# WaterMonitor.net
KiCad netlist of a schematic drawn in EAGLE
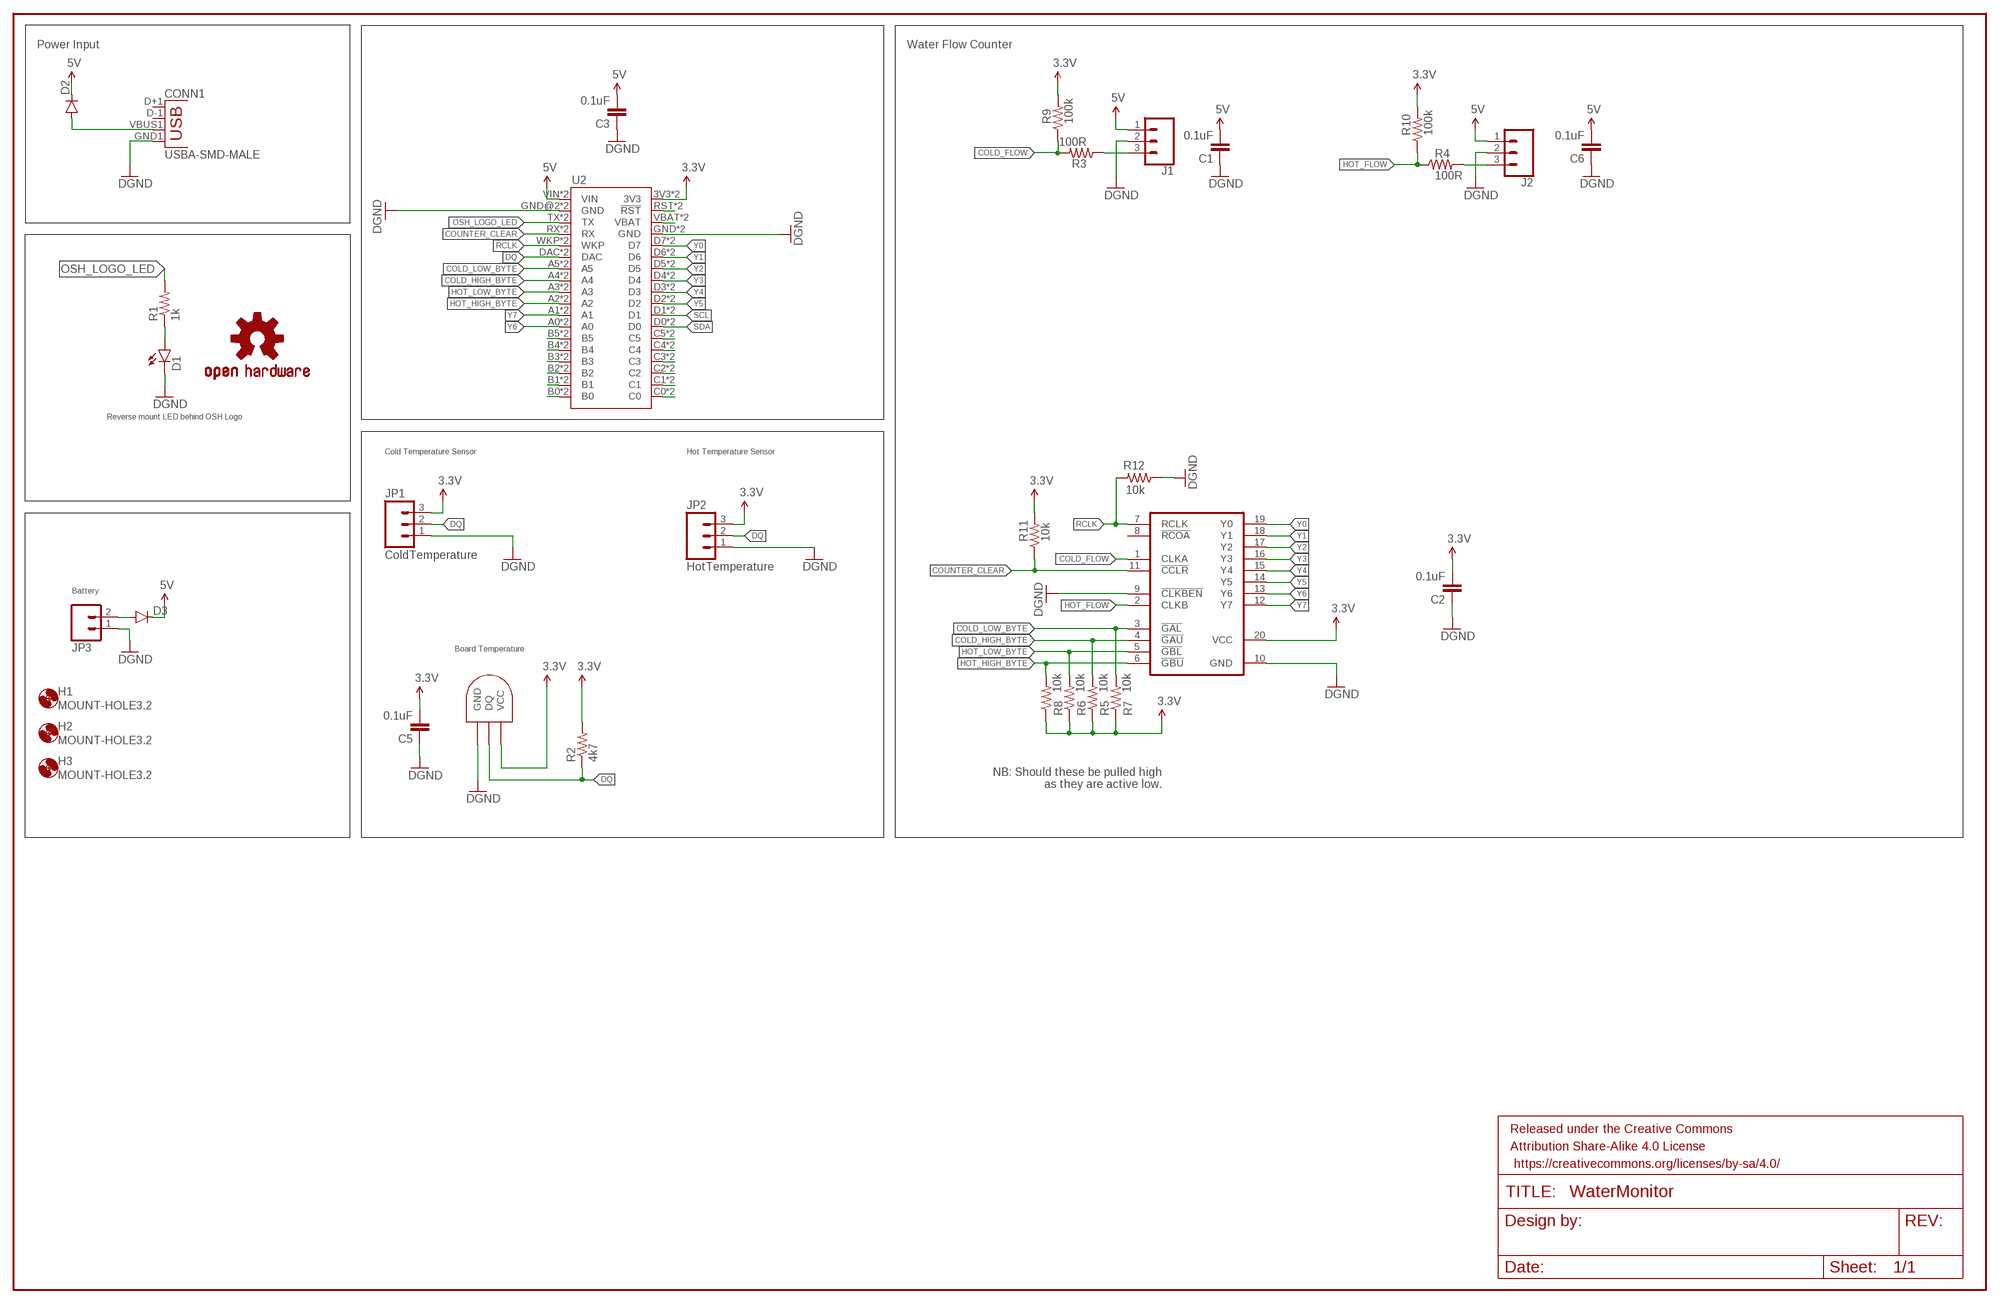
[diagram p0: schematic, sheet 1]

(export (version "E")
  (design (tool "Eeschema 10.0.6"))
  (components
    (comp (ref "C1")
      (value "0.1uF")
      (footprint "eagle-import:0805")
      (libsource (lib "eagle-import") (part "CAP0805"))
    )
    (comp (ref "C2")
      (value "0.1uF")
      (footprint "eagle-import:0805")
      (libsource (lib "eagle-import") (part "CAP0805"))
    )
    (comp (ref "C3")
      (value "0.1uF")
      (footprint "eagle-import:0805")
      (libsource (lib "eagle-import") (part "CAP0805"))
    )
    (comp (ref "C5")
      (value "0.1uF")
      (footprint "eagle-import:0805")
      (libsource (lib "eagle-import") (part "CAP0805"))
    )
    (comp (ref "C6")
      (value "0.1uF")
      (footprint "eagle-import:0805")
      (libsource (lib "eagle-import") (part "CAP0805"))
    )
    (comp (ref "CONN1")
      (value "USBA-SMD-MALE")
      (footprint "eagle-import:USB-A-SMT-MALE")
      (libsource (lib "eagle-import") (part "USBA-SMD-MALE"))
    )
    (comp (ref "D1")
      (value "LED1206-BOTTOM")
      (footprint "eagle-import:LED-1206-BOTTOM")
      (libsource (lib "eagle-import") (part "LED1206-BOTTOM"))
    )
    (comp (ref "D2")
      (value "DIODESMA")
      (footprint "eagle-import:SMA-DIODE")
      (libsource (lib "eagle-import") (part "DIODESMA"))
    )
    (comp (ref "D3")
      (value "DIODESMA")
      (footprint "eagle-import:SMA-DIODE")
      (libsource (lib "eagle-import") (part "DIODESMA"))
    )
    (comp (ref "FRAME2")
      (value "FRAME-LEDGER")
      (footprint "eagle-import:CREATIVE_COMMONS")
      (libsource (lib "eagle-import") (part "FRAME-LEDGER"))
    )
    (comp (ref "H1")
      (value "MOUNT-HOLE3.2")
      (footprint "eagle-import:3,2")
      (libsource (lib "eagle-import") (part "MOUNT-HOLE3.2"))
    )
    (comp (ref "H2")
      (value "MOUNT-HOLE3.2")
      (footprint "eagle-import:3,2")
      (libsource (lib "eagle-import") (part "MOUNT-HOLE3.2"))
    )
    (comp (ref "H3")
      (value "MOUNT-HOLE3.2")
      (footprint "eagle-import:3,2")
      (libsource (lib "eagle-import") (part "MOUNT-HOLE3.2"))
    )
    (comp (ref "J1")
      (value "CONN_03JST-HX-PTH-VERT")
      (footprint "eagle-import:JST-HX-3-PTH-VERT")
      (libsource (lib "eagle-import") (part "CONN_03JST-HX-PTH-VERT"))
    )
    (comp (ref "J2")
      (value "CONN_03JST-HX-PTH-VERT")
      (footprint "eagle-import:JST-HX-3-PTH-VERT")
      (libsource (lib "eagle-import") (part "CONN_03JST-HX-PTH-VERT"))
    )
    (comp (ref "JP1")
      (value "ColdTemperature")
      (footprint "eagle-import:MOLEX-1X3")
      (libsource (lib "eagle-import") (part "M03POLAR"))
    )
    (comp (ref "JP2")
      (value "HotTemperature")
      (footprint "eagle-import:MOLEX-1X3")
      (libsource (lib "eagle-import") (part "M03POLAR"))
    )
    (comp (ref "JP3")
      (value "M02-JST-2MM-SMT")
      (footprint "eagle-import:JST-2-SMD")
      (libsource (lib "eagle-import") (part "M02-JST-2MM-SMT"))
    )
    (comp (ref "LOGO1")
      (value "OSHW-LOGOM")
      (footprint "eagle-import:OSHW-LOGO-M")
      (libsource (lib "eagle-import") (part "OSHW-LOGOM"))
    )
    (comp (ref "R1")
      (value "1k")
      (footprint "eagle-import:1206")
      (libsource (lib "eagle-import") (part "RESISTOR1206"))
    )
    (comp (ref "R2")
      (value "4k7")
      (footprint "eagle-import:0805")
      (libsource (lib "eagle-import") (part "RESISTOR0805-RES"))
    )
    (comp (ref "R3")
      (value "100R")
      (footprint "eagle-import:0805")
      (libsource (lib "eagle-import") (part "RESISTOR0805-RES"))
    )
    (comp (ref "R4")
      (value "100R")
      (footprint "eagle-import:0805")
      (libsource (lib "eagle-import") (part "RESISTOR0805-RES"))
    )
    (comp (ref "R5")
      (value "10k")
      (footprint "eagle-import:0805")
      (libsource (lib "eagle-import") (part "RESISTOR0805-RES"))
    )
    (comp (ref "R6")
      (value "10k")
      (footprint "eagle-import:0805")
      (libsource (lib "eagle-import") (part "RESISTOR0805-RES"))
    )
    (comp (ref "R7")
      (value "10k")
      (footprint "eagle-import:0805")
      (libsource (lib "eagle-import") (part "RESISTOR0805-RES"))
    )
    (comp (ref "R8")
      (value "10k")
      (footprint "eagle-import:0805")
      (libsource (lib "eagle-import") (part "RESISTOR0805-RES"))
    )
    (comp (ref "R9")
      (value "100k")
      (footprint "eagle-import:0805")
      (libsource (lib "eagle-import") (part "RESISTOR0805-RES"))
    )
    (comp (ref "R10")
      (value "100k")
      (footprint "eagle-import:0805")
      (libsource (lib "eagle-import") (part "RESISTOR0805-RES"))
    )
    (comp (ref "R11")
      (value "10k")
      (footprint "eagle-import:0805")
      (libsource (lib "eagle-import") (part "RESISTOR0805-RES"))
    )
    (comp (ref "R12")
      (value "10k")
      (footprint "eagle-import:0805")
      (libsource (lib "eagle-import") (part "RESISTOR0805-RES"))
    )
    (comp (ref "U1")
      (value "SN74LV8154PW")
      (footprint "eagle-import:TSSOP20")
      (libsource (lib "eagle-import") (part "SN74LV8154PW"))
    )
    (comp (ref "U2")
      (value "ELECTRONDUALNAMED")
      (footprint "eagle-import:ELECTRON_SIMPLE_SILK_NAMES_DUAL")
      (libsource (lib "eagle-import") (part "ELECTRONDUALNAMED"))
    )
    (comp (ref "U4")
      (value "DS1820SOIC")
      (footprint "eagle-import:DS18B20_SOIC")
      (libsource (lib "eagle-import") (part "DS1820SOIC"))
    )
  )
  (nets
    (net (code "1") (name "3.3V") (class "Default")
      (node (ref "C2") (pin "2") (pinfunction "2_2") (pintype "passive"))
      (node (ref "C5") (pin "2") (pinfunction "2_2") (pintype "passive"))
      (node (ref "JP1") (pin "3") (pinfunction "3_3") (pintype "passive"))
      (node (ref "JP2") (pin "3") (pinfunction "3_3") (pintype "passive"))
      (node (ref "R10") (pin "2") (pinfunction "2_2") (pintype "passive"))
      (node (ref "R11") (pin "2") (pinfunction "2_2") (pintype "passive"))
      (node (ref "R2") (pin "2") (pinfunction "2_2") (pintype "passive"))
      (node (ref "R5") (pin "1") (pinfunction "1_1") (pintype "passive"))
      (node (ref "R6") (pin "1") (pinfunction "1_1") (pintype "passive"))
      (node (ref "R7") (pin "1") (pinfunction "1_1") (pintype "passive"))
      (node (ref "R8") (pin "1") (pinfunction "1_1") (pintype "passive"))
      (node (ref "R9") (pin "2") (pinfunction "2_2") (pintype "passive"))
      (node (ref "U1") (pin "20") (pinfunction "VCC_20") (pintype "power_in"))
      (node (ref "U2") (pin "3V3") (pinfunction "3V3_3V3") (pintype "power_in"))
      (node (ref "U2") (pin "3V3_1") (pinfunction "3V3_3V3_1") (pintype "power_in"))
      (node (ref "U4") (pin "VCC") (pinfunction "VCC_VCC") (pintype "power_in"))
    )
    (net (code "2") (name "5V") (class "Default")
      (node (ref "C1") (pin "2") (pinfunction "2_2") (pintype "passive"))
      (node (ref "C3") (pin "2") (pinfunction "2_2") (pintype "passive"))
      (node (ref "C6") (pin "2") (pinfunction "2_2") (pintype "passive"))
      (node (ref "D2") (pin "C") (pinfunction "C_C") (pintype "passive"))
      (node (ref "D3") (pin "C") (pinfunction "C_C") (pintype "passive"))
      (node (ref "J1") (pin "1") (pinfunction "1_1") (pintype "passive"))
      (node (ref "J2") (pin "1") (pinfunction "1_1") (pintype "passive"))
      (node (ref "U2") (pin "VIN") (pinfunction "VIN_VIN") (pintype "power_in"))
      (node (ref "U2") (pin "VIN_1B") (pinfunction "VIN_VIN_1B") (pintype "power_in"))
    )
    (net (code "3") (name "COLD_FLOW") (class "Default")
      (node (ref "R3") (pin "2") (pinfunction "2_2") (pintype "passive"))
      (node (ref "R9") (pin "1") (pinfunction "1_1") (pintype "passive"))
      (node (ref "U1") (pin "1") (pinfunction "CLKA_1") (pintype "input"))
    )
    (net (code "4") (name "COLD_HIGH_BYTE") (class "Default")
      (node (ref "R5") (pin "2") (pinfunction "2_2") (pintype "passive"))
      (node (ref "U1") (pin "4") (pinfunction "~{GAU}_4") (pintype "input"))
      (node (ref "U2") (pin "A4") (pinfunction "A4_A4") (pintype "bidirectional"))
      (node (ref "U2") (pin "A4_1") (pinfunction "A4_A4_1") (pintype "bidirectional"))
    )
    (net (code "5") (name "COLD_LOW_BYTE") (class "Default")
      (node (ref "R7") (pin "2") (pinfunction "2_2") (pintype "passive"))
      (node (ref "U1") (pin "3") (pinfunction "~{GAL}_3") (pintype "input"))
      (node (ref "U2") (pin "A5") (pinfunction "A5_A5") (pintype "bidirectional"))
      (node (ref "U2") (pin "A5_1") (pinfunction "A5_A5_1") (pintype "bidirectional"))
    )
    (net (code "6") (name "COUNTER_CLEAR") (class "Default")
      (node (ref "R11") (pin "1") (pinfunction "1_1") (pintype "passive"))
      (node (ref "U1") (pin "11") (pinfunction "~{CCLR}_11") (pintype "input"))
      (node (ref "U2") (pin "RX") (pinfunction "RX_RX") (pintype "bidirectional"))
      (node (ref "U2") (pin "RX_1") (pinfunction "RX_RX_1") (pintype "bidirectional"))
    )
    (net (code "7") (name "DGND") (class "Default")
      (node (ref "C1") (pin "1") (pinfunction "1_1") (pintype "passive"))
      (node (ref "C2") (pin "1") (pinfunction "1_1") (pintype "passive"))
      (node (ref "C3") (pin "1") (pinfunction "1_1") (pintype "passive"))
      (node (ref "C5") (pin "1") (pinfunction "1_1") (pintype "passive"))
      (node (ref "C6") (pin "1") (pinfunction "1_1") (pintype "passive"))
      (node (ref "CONN1") (pin "GND1") (pinfunction "GND_GND1") (pintype "bidirectional"))
      (node (ref "D1") (pin "C") (pinfunction "C_C") (pintype "passive"))
      (node (ref "J1") (pin "2") (pinfunction "2_2") (pintype "passive"))
      (node (ref "J2") (pin "2") (pinfunction "2_2") (pintype "passive"))
      (node (ref "JP1") (pin "1") (pinfunction "1_1") (pintype "passive"))
      (node (ref "JP2") (pin "1") (pinfunction "1_1") (pintype "passive"))
      (node (ref "JP3") (pin "1") (pinfunction "2_1") (pintype "passive"))
      (node (ref "R12") (pin "1") (pinfunction "1_1") (pintype "passive"))
      (node (ref "U1") (pin "10") (pinfunction "GND_10") (pintype "power_in"))
      (node (ref "U1") (pin "9") (pinfunction "~{CLKBEN}_9") (pintype "input"))
      (node (ref "U2") (pin "GND") (pinfunction "GND_GND") (pintype "power_in"))
      (node (ref "U2") (pin "GND@2") (pinfunction "GND_GND@2") (pintype "power_in"))
      (node (ref "U2") (pin "GND_1") (pinfunction "GND_GND_1") (pintype "power_in"))
      (node (ref "U2") (pin "GND_1B") (pinfunction "GND_GND_1B") (pintype "power_in"))
      (node (ref "U4") (pin "GND") (pinfunction "GND_GND") (pintype "power_in"))
    )
    (net (code "8") (name "DQ") (class "Default")
      (node (ref "JP1") (pin "2") (pinfunction "2_2") (pintype "passive"))
      (node (ref "JP2") (pin "2") (pinfunction "2_2") (pintype "passive"))
      (node (ref "R2") (pin "1") (pinfunction "1_1") (pintype "passive"))
      (node (ref "U2") (pin "DAC") (pinfunction "DAC_DAC") (pintype "bidirectional"))
      (node (ref "U2") (pin "DAC_1") (pinfunction "DAC_DAC_1") (pintype "bidirectional"))
      (node (ref "U4") (pin "DQ") (pinfunction "DQ_DQ") (pintype "bidirectional"))
    )
    (net (code "9") (name "HOT_FLOW") (class "Default")
      (node (ref "R10") (pin "1") (pinfunction "1_1") (pintype "passive"))
      (node (ref "R4") (pin "1") (pinfunction "1_1") (pintype "passive"))
      (node (ref "U1") (pin "2") (pinfunction "CLKB_2") (pintype "input"))
    )
    (net (code "10") (name "HOT_HIGH_BYTE") (class "Default")
      (node (ref "R8") (pin "2") (pinfunction "2_2") (pintype "passive"))
      (node (ref "U1") (pin "6") (pinfunction "~{GBU}_6") (pintype "input"))
      (node (ref "U2") (pin "A2") (pinfunction "A2_A2") (pintype "bidirectional"))
      (node (ref "U2") (pin "A2_1") (pinfunction "A2_A2_1") (pintype "bidirectional"))
    )
    (net (code "11") (name "HOT_LOW_BYTE") (class "Default")
      (node (ref "R6") (pin "2") (pinfunction "2_2") (pintype "passive"))
      (node (ref "U1") (pin "5") (pinfunction "~{GBL}_5") (pintype "input"))
      (node (ref "U2") (pin "A3") (pinfunction "A3_A3") (pintype "bidirectional"))
      (node (ref "U2") (pin "A3_1") (pinfunction "A3_A3_1") (pintype "bidirectional"))
    )
    (net (code "12") (name "Net-(CONN1-VBUS)") (class "Default")
      (node (ref "CONN1") (pin "VBUS1") (pinfunction "VBUS_VBUS1") (pintype "bidirectional"))
      (node (ref "D2") (pin "A") (pinfunction "A_A") (pintype "passive"))
    )
    (net (code "13") (name "Net-(D1-PadA)") (class "Default")
      (node (ref "D1") (pin "A") (pinfunction "A_A") (pintype "passive"))
      (node (ref "R1") (pin "1") (pinfunction "1_1") (pintype "passive"))
    )
    (net (code "14") (name "Net-(J1-Pad3)") (class "Default")
      (node (ref "J1") (pin "3") (pinfunction "3_3") (pintype "passive"))
      (node (ref "R3") (pin "1") (pinfunction "1_1") (pintype "passive"))
    )
    (net (code "15") (name "Net-(J2-Pad3)") (class "Default")
      (node (ref "J2") (pin "3") (pinfunction "3_3") (pintype "passive"))
      (node (ref "R4") (pin "2") (pinfunction "2_2") (pintype "passive"))
    )
    (net (code "16") (name "Net-(JP3-1)") (class "Default")
      (node (ref "D3") (pin "A") (pinfunction "A_A") (pintype "passive"))
      (node (ref "JP3") (pin "2") (pinfunction "1_2") (pintype "passive"))
    )
    (net (code "17") (name "Net-(U2-B0-PadB0_1)") (class "Default")
      (node (ref "U2") (pin "B0") (pinfunction "B0_B0") (pintype "bidirectional"))
      (node (ref "U2") (pin "B0_1") (pinfunction "B0_B0_1") (pintype "bidirectional"))
    )
    (net (code "18") (name "Net-(U2-B1-PadB1_1)") (class "Default")
      (node (ref "U2") (pin "B1") (pinfunction "B1_B1") (pintype "bidirectional"))
      (node (ref "U2") (pin "B1_1") (pinfunction "B1_B1_1") (pintype "bidirectional"))
    )
    (net (code "19") (name "Net-(U2-B2-PadB2_1)") (class "Default")
      (node (ref "U2") (pin "B2") (pinfunction "B2_B2") (pintype "bidirectional"))
      (node (ref "U2") (pin "B2_1") (pinfunction "B2_B2_1") (pintype "bidirectional"))
    )
    (net (code "20") (name "Net-(U2-B3-PadB3_1)") (class "Default")
      (node (ref "U2") (pin "B3") (pinfunction "B3_B3") (pintype "bidirectional"))
      (node (ref "U2") (pin "B3_1") (pinfunction "B3_B3_1") (pintype "bidirectional"))
    )
    (net (code "21") (name "Net-(U2-B4-PadB4_1)") (class "Default")
      (node (ref "U2") (pin "B4") (pinfunction "B4_B4") (pintype "bidirectional"))
      (node (ref "U2") (pin "B4_1") (pinfunction "B4_B4_1") (pintype "bidirectional"))
    )
    (net (code "22") (name "Net-(U2-B5-PadB5_1)") (class "Default")
      (node (ref "U2") (pin "B5") (pinfunction "B5_B5") (pintype "bidirectional"))
      (node (ref "U2") (pin "B5_1") (pinfunction "B5_B5_1") (pintype "bidirectional"))
    )
    (net (code "23") (name "Net-(U2-C0-PadC0_1)") (class "Default")
      (node (ref "U2") (pin "C0") (pinfunction "C0_C0") (pintype "bidirectional"))
      (node (ref "U2") (pin "C0_1") (pinfunction "C0_C0_1") (pintype "bidirectional"))
    )
    (net (code "24") (name "Net-(U2-C1-PadC1_1)") (class "Default")
      (node (ref "U2") (pin "C1") (pinfunction "C1_C1") (pintype "bidirectional"))
      (node (ref "U2") (pin "C1_1") (pinfunction "C1_C1_1") (pintype "bidirectional"))
    )
    (net (code "25") (name "Net-(U2-C2-PadC2_1)") (class "Default")
      (node (ref "U2") (pin "C2") (pinfunction "C2_C2") (pintype "bidirectional"))
      (node (ref "U2") (pin "C2_1") (pinfunction "C2_C2_1") (pintype "bidirectional"))
    )
    (net (code "26") (name "Net-(U2-C3-PadC3_1)") (class "Default")
      (node (ref "U2") (pin "C3") (pinfunction "C3_C3") (pintype "bidirectional"))
      (node (ref "U2") (pin "C3_1") (pinfunction "C3_C3_1") (pintype "bidirectional"))
    )
    (net (code "27") (name "Net-(U2-C4-PadC4_1)") (class "Default")
      (node (ref "U2") (pin "C4") (pinfunction "C4_C4") (pintype "bidirectional"))
      (node (ref "U2") (pin "C4_1") (pinfunction "C4_C4_1") (pintype "bidirectional"))
    )
    (net (code "28") (name "Net-(U2-C5-PadC5_1)") (class "Default")
      (node (ref "U2") (pin "C5") (pinfunction "C5_C5") (pintype "bidirectional"))
      (node (ref "U2") (pin "C5_1") (pinfunction "C5_C5_1") (pintype "bidirectional"))
    )
    (net (code "29") (name "Net-(U2-PadVBAT)") (class "Default")
      (node (ref "U2") (pin "VBAT") (pinfunction "VBAT_VBAT") (pintype "passive"))
      (node (ref "U2") (pin "VBATT_1") (pinfunction "VBAT_VBATT_1") (pintype "passive"))
    )
    (net (code "30") (name "Net-(U2-~{RST}-PadRST)") (class "Default")
      (node (ref "U2") (pin "RST") (pinfunction "~{RST}_RST") (pintype "bidirectional"))
      (node (ref "U2") (pin "RST_1") (pinfunction "~{RST}_RST_1") (pintype "bidirectional"))
    )
    (net (code "31") (name "OSH_LOGO_LED") (class "Default")
      (node (ref "R1") (pin "2") (pinfunction "2_2") (pintype "passive"))
      (node (ref "U2") (pin "TX") (pinfunction "TX_TX") (pintype "bidirectional"))
      (node (ref "U2") (pin "TX_1") (pinfunction "TX_TX_1") (pintype "bidirectional"))
    )
    (net (code "32") (name "RCLK") (class "Default")
      (node (ref "R12") (pin "2") (pinfunction "2_2") (pintype "passive"))
      (node (ref "U1") (pin "7") (pinfunction "RCLK_7") (pintype "input"))
      (node (ref "U2") (pin "WKP") (pinfunction "WKP_WKP") (pintype "bidirectional"))
      (node (ref "U2") (pin "WKP_1") (pinfunction "WKP_WKP_1") (pintype "bidirectional"))
    )
    (net (code "33") (name "SCL") (class "Default")
      (node (ref "U2") (pin "D1") (pinfunction "D1_D1") (pintype "bidirectional"))
      (node (ref "U2") (pin "D1_1") (pinfunction "D1_D1_1") (pintype "bidirectional"))
    )
    (net (code "34") (name "SDA") (class "Default")
      (node (ref "U2") (pin "D0") (pinfunction "D0_D0") (pintype "bidirectional"))
      (node (ref "U2") (pin "D0_1") (pinfunction "D0_D0_1") (pintype "bidirectional"))
    )
    (net (code "35") (name "Y0") (class "Default")
      (node (ref "U1") (pin "19") (pinfunction "Y0_19") (pintype "output"))
      (node (ref "U2") (pin "D7") (pinfunction "D7_D7") (pintype "bidirectional"))
      (node (ref "U2") (pin "D7_1") (pinfunction "D7_D7_1") (pintype "bidirectional"))
    )
    (net (code "36") (name "Y1") (class "Default")
      (node (ref "U1") (pin "18") (pinfunction "Y1_18") (pintype "output"))
      (node (ref "U2") (pin "D6") (pinfunction "D6_D6") (pintype "bidirectional"))
      (node (ref "U2") (pin "D6_1") (pinfunction "D6_D6_1") (pintype "bidirectional"))
    )
    (net (code "37") (name "Y2") (class "Default")
      (node (ref "U1") (pin "17") (pinfunction "Y2_17") (pintype "output"))
      (node (ref "U2") (pin "D5") (pinfunction "D5_D5") (pintype "bidirectional"))
      (node (ref "U2") (pin "D5_1") (pinfunction "D5_D5_1") (pintype "bidirectional"))
    )
    (net (code "38") (name "Y3") (class "Default")
      (node (ref "U1") (pin "16") (pinfunction "Y3_16") (pintype "output"))
      (node (ref "U2") (pin "D4") (pinfunction "D4_D4") (pintype "bidirectional"))
      (node (ref "U2") (pin "D4_1") (pinfunction "D4_D4_1") (pintype "bidirectional"))
    )
    (net (code "39") (name "Y4") (class "Default")
      (node (ref "U1") (pin "15") (pinfunction "Y4_15") (pintype "output"))
      (node (ref "U2") (pin "D3") (pinfunction "D3_D3") (pintype "bidirectional"))
      (node (ref "U2") (pin "D3_1") (pinfunction "D3_D3_1") (pintype "bidirectional"))
    )
    (net (code "40") (name "Y5") (class "Default")
      (node (ref "U1") (pin "14") (pinfunction "Y5_14") (pintype "output"))
      (node (ref "U2") (pin "D2") (pinfunction "D2_D2") (pintype "bidirectional"))
      (node (ref "U2") (pin "D2_1") (pinfunction "D2_D2_1") (pintype "bidirectional"))
    )
    (net (code "41") (name "Y6") (class "Default")
      (node (ref "U1") (pin "13") (pinfunction "Y6_13") (pintype "output"))
      (node (ref "U2") (pin "A0") (pinfunction "A0_A0") (pintype "bidirectional"))
      (node (ref "U2") (pin "A0_1") (pinfunction "A0_A0_1") (pintype "bidirectional"))
    )
    (net (code "42") (name "Y7") (class "Default")
      (node (ref "U1") (pin "12") (pinfunction "Y7_12") (pintype "output"))
      (node (ref "U2") (pin "A1") (pinfunction "A1_A1") (pintype "bidirectional"))
      (node (ref "U2") (pin "A1_1") (pinfunction "A1_A1_1") (pintype "bidirectional"))
    )
    (net (code "43") (name "unconnected-(CONN1-D+-PadD+1)") (class "Default")
      (node (ref "CONN1") (pin "D+1") (pinfunction "D+_D+1") (pintype "bidirectional"))
    )
    (net (code "44") (name "unconnected-(CONN1-D--PadD-1)") (class "Default")
      (node (ref "CONN1") (pin "D-1") (pinfunction "D-_D-1") (pintype "bidirectional"))
    )
    (net (code "45") (name "unconnected-(U1-~{RCOA}-Pad8)") (class "Default")
      (node (ref "U1") (pin "8") (pinfunction "~{RCOA}_8") (pintype "output"))
    )
  )
)
